# stm32f103cbt6.net
KiCad netlist of a schematic drawn in Altium Designer
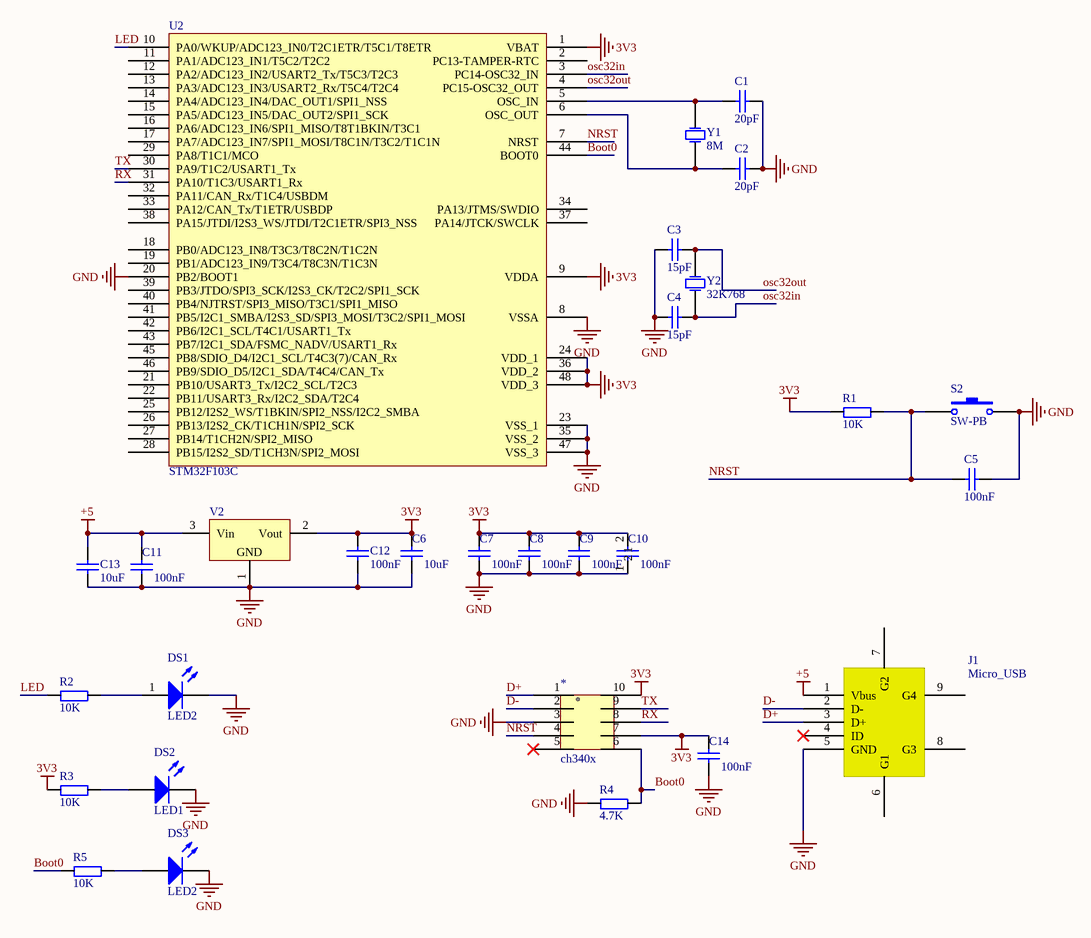
[diagram p0: stm32f103cbt6.SchDoc]

(export (version "E")
  (design (tool "Eeschema 10.0.6"))
  (components
    (comp (ref "*")
      (value "ch340x")
      (footprint "MSOP-10_L3.0-W3.0-P0.50-LS5.0-BL")
      (libsource (lib "常用元件库") (part "ch340x"))
    )
    (comp (ref "C1")
      (value "20pF")
      (footprint "C0603")
      (description "Capacitor")
      (fields (field (name "PUBLISHER") "Altium Limited"))
      (libsource (lib "Miscellaneous Devices") (part "Cap"))
    )
    (comp (ref "C2")
      (value "20pF")
      (footprint "C0603")
      (description "Capacitor")
      (fields (field (name "PUBLISHER") "Altium Limited"))
      (libsource (lib "Miscellaneous Devices") (part "Cap"))
    )
    (comp (ref "C3")
      (value "15pF")
      (footprint "C0603")
      (description "Capacitor")
      (fields (field (name "PUBLISHER") "Altium Limited"))
      (libsource (lib "Miscellaneous Devices") (part "Cap"))
    )
    (comp (ref "C4")
      (value "15pF")
      (footprint "C0603")
      (description "Capacitor")
      (fields (field (name "PUBLISHER") "Altium Limited"))
      (libsource (lib "Miscellaneous Devices") (part "Cap"))
    )
    (comp (ref "C5")
      (value "100nF")
      (footprint "C0603")
      (description "Capacitor")
      (fields (field (name "PUBLISHER") "Altium Limited"))
      (libsource (lib "Miscellaneous Devices") (part "Cap"))
    )
    (comp (ref "C6")
      (value "10uF")
      (footprint "C0603")
      (description "Capacitor")
      (fields (field (name "PUBLISHER") "Altium Limited"))
      (libsource (lib "Miscellaneous Devices") (part "Cap"))
    )
    (comp (ref "C7")
      (value "100nF")
      (footprint "C0603")
      (description "Capacitor")
      (fields (field (name "PUBLISHER") "Altium Limited"))
      (libsource (lib "Miscellaneous Devices") (part "Cap"))
    )
    (comp (ref "C8")
      (value "100nF")
      (footprint "C0603")
      (description "Capacitor")
      (fields (field (name "PUBLISHER") "Altium Limited"))
      (libsource (lib "Miscellaneous Devices") (part "Cap"))
    )
    (comp (ref "C9")
      (value "100nF")
      (footprint "C0603")
      (description "Capacitor")
      (fields (field (name "PUBLISHER") "Altium Limited"))
      (libsource (lib "Miscellaneous Devices") (part "Cap"))
    )
    (comp (ref "C10")
      (value "100nF")
      (footprint "C0603")
      (description "Capacitor")
      (fields (field (name "PUBLISHER") "Altium Limited"))
      (libsource (lib "") (part "Cap_1"))
    )
    (comp (ref "C11")
      (value "100nF")
      (footprint "C0603")
      (description "Capacitor")
      (fields (field (name "PUBLISHER") "Altium Limited"))
      (libsource (lib "Miscellaneous Devices") (part "Cap"))
    )
    (comp (ref "C12")
      (value "100nF")
      (footprint "C0603")
      (description "Capacitor")
      (fields (field (name "PUBLISHER") "Altium Limited"))
      (libsource (lib "Miscellaneous Devices") (part "Cap"))
    )
    (comp (ref "C13")
      (value "10uF")
      (footprint "C0603")
      (description "Capacitor")
      (fields (field (name "PUBLISHER") "Altium Limited"))
      (libsource (lib "Miscellaneous Devices") (part "Cap"))
    )
    (comp (ref "C14")
      (value "100nF")
      (footprint "C0603")
      (description "Capacitor")
      (fields (field (name "PUBLISHER") "Altium Limited"))
      (libsource (lib "Miscellaneous Devices") (part "Cap"))
    )
    (comp (ref "DS1")
      (value "LED2")
      (footprint "SMDLED")
      (description "Typical RED, GREEN, YELLOW, AMBER GaAs LED")
      (fields (field (name "PUBLISHER") "Altium Limited"))
      (libsource (lib "") (part "LED2_1"))
    )
    (comp (ref "DS2")
      (value "LED1")
      (footprint "SMDLED")
      (description "Typical RED, GREEN, YELLOW, AMBER GaAs LED")
      (fields (field (name "PUBLISHER") "Altium Limited"))
      (libsource (lib "朱雀F103开发板封装库") (part "LED2"))
    )
    (comp (ref "DS3")
      (value "LED2")
      (footprint "SMDLED")
      (description "Typical RED, GREEN, YELLOW, AMBER GaAs LED")
      (fields (field (name "PUBLISHER") "Altium Limited"))
      (libsource (lib "朱雀F103开发板封装库") (part "LED2"))
    )
    (comp (ref "J1")
      (value "Micro_USB")
      (footprint "MICRO-USB-SMD_MICROQTJ")
      (libsource (lib "Dr.Xiong_20160818") (part "Micro_USB"))
    )
    (comp (ref "R1") (value "10K") (footprint "0603P") (libsource (lib "朱雀F103开发板封装库") (part "R")))
    (comp (ref "R2") (value "10K") (footprint "0603P") (libsource (lib "朱雀F103开发板封装库") (part "R")))
    (comp (ref "R3") (value "10K") (footprint "0603P") (libsource (lib "朱雀F103开发板封装库") (part "R")))
    (comp (ref "R4") (value "4.7K") (footprint "0603P") (libsource (lib "朱雀F103开发板封装库") (part "R")))
    (comp (ref "R5") (value "10K") (footprint "0603P") (libsource (lib "朱雀F103开发板封装库") (part "R")))
    (comp (ref "S2")
      (value "SW-PB")
      (footprint "KEY-SMD_L3.9-W3.0-LS5.0")
      (description "Switch")
      (fields (field (name "PUBLISHER") "Altium Limited"))
      (libsource (lib "Miscellaneous Devices") (part "SW-PB"))
    )
    (comp (ref "U2")
      (value "STM32F103C")
      (footprint "LQFP-48_M")
      (description "STM32单片机48引脚")
      (libsource (lib "STM32芯片") (part "STM32F103C"))
    )
    (comp (ref "V2")
      (value "AMS1117-3V3")
      (footprint "SOT223_L")
      (description "三端稳压芯片")
      (fields (field (name "版权归属") "源创客"))
      (libsource (lib "1.3   - 电源类芯片") (part "AMS1117"))
    )
    (comp (ref "Y1")
      (value "8M")
      (footprint "XTAL(5032)")
      (description "Crystal Oscillator")
      (fields (field (name "PUBLISHER") "Altium Limited"))
      (libsource (lib "Miscellaneous Devices") (part "XTAL"))
    )
    (comp (ref "Y2")
      (value "32K768")
      (footprint "CRYSTAL-SMD_L3.2-W1.5-1")
      (description "Crystal Oscillator")
      (fields (field (name "PUBLISHER") "Altium Limited"))
      (libsource (lib "Miscellaneous Devices") (part "XTAL"))
    )
  )
  (nets
    (net (code "1") (name "+5") (class "Default")
      (node (ref "C11") (pin "2") (pinfunction "2_2") (pintype "passive"))
      (node (ref "C13") (pin "2") (pinfunction "2_2") (pintype "passive"))
      (node (ref "J1") (pin "1") (pinfunction "Vbus_1") (pintype "passive"))
      (node (ref "V2") (pin "3") (pinfunction "Vin_3") (pintype "passive"))
    )
    (net (code "2") (name "/Boot0") (class "Default")
      (node (ref "*") (pin "6") (pinfunction "DTR#_6") (pintype "passive"))
      (node (ref "R4") (pin "2") (pintype "passive"))
      (node (ref "R5") (pin "1") (pintype "passive"))
      (node (ref "U2") (pin "44") (pinfunction "BOOT0_44") (pintype "passive"))
    )
    (net (code "3") (name "/D+") (class "Default")
      (node (ref "*") (pin "1") (pinfunction "UD+_1") (pintype "passive"))
      (node (ref "J1") (pin "3") (pinfunction "D+_3") (pintype "passive"))
    )
    (net (code "4") (name "/D-") (class "Default")
      (node (ref "*") (pin "2") (pinfunction "UD-_2") (pintype "passive"))
      (node (ref "J1") (pin "2") (pinfunction "D-_2") (pintype "passive"))
    )
    (net (code "5") (name "/LED") (class "Default")
      (node (ref "R2") (pin "1") (pintype "passive"))
      (node (ref "U2") (pin "10") (pinfunction "PA0/WKUP/ADC123_IN0/T2C1ETR/T5C1/T8ETR_10") (pintype "passive"))
    )
    (net (code "6") (name "/NRST") (class "Default")
      (node (ref "*") (pin "4") (pinfunction "RTS#_4") (pintype "passive"))
      (node (ref "C5") (pin "1") (pinfunction "1_1") (pintype "passive"))
      (node (ref "R1") (pin "2") (pintype "passive"))
      (node (ref "S2") (pin "1") (pinfunction "1_1") (pintype "passive"))
      (node (ref "U2") (pin "7") (pinfunction "NRST_7") (pintype "passive"))
    )
    (net (code "7") (name "/RX") (class "Default")
      (node (ref "*") (pin "8") (pinfunction "TXD_8") (pintype "passive"))
      (node (ref "U2") (pin "31") (pinfunction "PA10/T1C3/USART1_Rx_31") (pintype "passive"))
    )
    (net (code "8") (name "/TX") (class "Default")
      (node (ref "*") (pin "9") (pinfunction "RXD_9") (pintype "passive"))
      (node (ref "U2") (pin "30") (pinfunction "PA9/T1C2/USART1_Tx_30") (pintype "passive"))
    )
    (net (code "9") (name "/osc32in") (class "Default")
      (node (ref "C4") (pin "2") (pinfunction "2_2") (pintype "passive"))
      (node (ref "U2") (pin "3") (pinfunction "PC14-OSC32_IN_3") (pintype "passive"))
      (node (ref "Y2") (pin "1") (pinfunction "OSC1_1") (pintype "passive"))
    )
    (net (code "10") (name "/osc32out") (class "Default")
      (node (ref "C3") (pin "2") (pinfunction "2_2") (pintype "passive"))
      (node (ref "U2") (pin "4") (pinfunction "PC15-OSC32_OUT_4") (pintype "passive"))
      (node (ref "Y2") (pin "2") (pinfunction "OSC2_2") (pintype "passive"))
    )
    (net (code "11") (name "3V3") (class "Default")
      (node (ref "*") (pin "10") (pinfunction "V3_10") (pintype "passive"))
      (node (ref "*") (pin "7") (pinfunction "VCC_7") (pintype "passive"))
      (node (ref "C10") (pin "2") (pinfunction "2_2") (pintype "passive"))
      (node (ref "C12") (pin "2") (pinfunction "2_2") (pintype "passive"))
      (node (ref "C14") (pin "2") (pinfunction "2_2") (pintype "passive"))
      (node (ref "C6") (pin "2") (pinfunction "2_2") (pintype "passive"))
      (node (ref "C7") (pin "2") (pinfunction "2_2") (pintype "passive"))
      (node (ref "C8") (pin "2") (pinfunction "2_2") (pintype "passive"))
      (node (ref "C9") (pin "2") (pinfunction "2_2") (pintype "passive"))
      (node (ref "R1") (pin "1") (pintype "passive"))
      (node (ref "R3") (pin "1") (pintype "passive"))
      (node (ref "U2") (pin "1") (pinfunction "VBAT_1") (pintype "passive"))
      (node (ref "U2") (pin "24") (pinfunction "VDD_1_24") (pintype "passive"))
      (node (ref "U2") (pin "36") (pinfunction "VDD_2_36") (pintype "passive"))
      (node (ref "U2") (pin "48") (pinfunction "VDD_3_48") (pintype "passive"))
      (node (ref "U2") (pin "9") (pinfunction "VDDA_9") (pintype "passive"))
      (node (ref "V2") (pin "2") (pinfunction "Vout_2") (pintype "passive"))
    )
    (net (code "12") (name "GND") (class "Default")
      (node (ref "*") (pin "3") (pinfunction "GND_3") (pintype "passive"))
      (node (ref "C1") (pin "2") (pinfunction "2_2") (pintype "passive"))
      (node (ref "C10") (pin "1") (pinfunction "1_1") (pintype "passive"))
      (node (ref "C11") (pin "1") (pinfunction "1_1") (pintype "passive"))
      (node (ref "C12") (pin "1") (pinfunction "1_1") (pintype "passive"))
      (node (ref "C13") (pin "1") (pinfunction "1_1") (pintype "passive"))
      (node (ref "C14") (pin "1") (pinfunction "1_1") (pintype "passive"))
      (node (ref "C2") (pin "2") (pinfunction "2_2") (pintype "passive"))
      (node (ref "C3") (pin "1") (pinfunction "1_1") (pintype "passive"))
      (node (ref "C4") (pin "1") (pinfunction "1_1") (pintype "passive"))
      (node (ref "C5") (pin "2") (pinfunction "2_2") (pintype "passive"))
      (node (ref "C6") (pin "1") (pinfunction "1_1") (pintype "passive"))
      (node (ref "C7") (pin "1") (pinfunction "1_1") (pintype "passive"))
      (node (ref "C8") (pin "1") (pinfunction "1_1") (pintype "passive"))
      (node (ref "C9") (pin "1") (pinfunction "1_1") (pintype "passive"))
      (node (ref "DS1") (pin "2") (pinfunction "K_2") (pintype "passive"))
      (node (ref "DS2") (pin "2") (pinfunction "K_2") (pintype "passive"))
      (node (ref "DS3") (pin "2") (pinfunction "K_2") (pintype "passive"))
      (node (ref "J1") (pin "5") (pinfunction "GND_5") (pintype "passive"))
      (node (ref "R4") (pin "1") (pintype "passive"))
      (node (ref "S2") (pin "2") (pinfunction "2_2") (pintype "passive"))
      (node (ref "U2") (pin "20") (pinfunction "PB2/BOOT1_20") (pintype "passive"))
      (node (ref "U2") (pin "23") (pinfunction "VSS_1_23") (pintype "passive"))
      (node (ref "U2") (pin "35") (pinfunction "VSS_2_35") (pintype "passive"))
      (node (ref "U2") (pin "47") (pinfunction "VSS_3_47") (pintype "passive"))
      (node (ref "U2") (pin "8") (pinfunction "VSSA_8") (pintype "passive"))
      (node (ref "V2") (pin "1") (pinfunction "GND_1") (pintype "passive"))
    )
    (net (code "13") (name "Net-(DS1-A)") (class "Default")
      (node (ref "DS1") (pin "1") (pinfunction "A_1") (pintype "passive"))
      (node (ref "R2") (pin "2") (pintype "passive"))
    )
    (net (code "14") (name "Net-(DS2-A)") (class "Default")
      (node (ref "DS2") (pin "1") (pinfunction "A_1") (pintype "passive"))
      (node (ref "R3") (pin "2") (pintype "passive"))
    )
    (net (code "15") (name "Net-(DS3-A)") (class "Default")
      (node (ref "DS3") (pin "1") (pinfunction "A_1") (pintype "passive"))
      (node (ref "R5") (pin "2") (pintype "passive"))
    )
    (net (code "16") (name "Net-(U2-OSC_IN)") (class "Default")
      (node (ref "C1") (pin "1") (pinfunction "1_1") (pintype "passive"))
      (node (ref "U2") (pin "5") (pinfunction "OSC_IN_5") (pintype "passive"))
      (node (ref "Y1") (pin "2") (pinfunction "OSC2_2") (pintype "passive"))
    )
    (net (code "17") (name "Net-(U2-OSC_OUT)") (class "Default")
      (node (ref "C2") (pin "1") (pinfunction "1_1") (pintype "passive"))
      (node (ref "U2") (pin "6") (pinfunction "OSC_OUT_6") (pintype "passive"))
      (node (ref "Y1") (pin "1") (pinfunction "OSC1_1") (pintype "passive"))
    )
    (net (code "18") (name "unconnected-(*-CTS#-Pad5)") (class "Default")
      (node (ref "*") (pin "5") (pinfunction "CTS#_5") (pintype "passive+no_connect"))
    )
    (net (code "19") (name "unconnected-(J1-G1-Pad6)") (class "Default")
      (node (ref "J1") (pin "6") (pinfunction "G1_6") (pintype "passive"))
    )
    (net (code "20") (name "unconnected-(J1-G2-Pad7)") (class "Default")
      (node (ref "J1") (pin "7") (pinfunction "G2_7") (pintype "passive"))
    )
    (net (code "21") (name "unconnected-(J1-G3-Pad8)") (class "Default")
      (node (ref "J1") (pin "8") (pinfunction "G3_8") (pintype "passive"))
    )
    (net (code "22") (name "unconnected-(J1-G4-Pad9)") (class "Default")
      (node (ref "J1") (pin "9") (pinfunction "G4_9") (pintype "passive"))
    )
    (net (code "23") (name "unconnected-(J1-ID-Pad4)") (class "Default")
      (node (ref "J1") (pin "4") (pinfunction "ID_4") (pintype "passive+no_connect"))
    )
    (net (code "24") (name "unconnected-(U2-PA1{slash}ADC123_IN1{slash}T5C2{slash}T2C2-Pad11)") (class "Default")
      (node (ref "U2") (pin "11") (pinfunction "PA1/ADC123_IN1/T5C2/T2C2_11") (pintype "passive"))
    )
    (net (code "25") (name "unconnected-(U2-PA2{slash}ADC123_IN2{slash}USART2_Tx{slash}T5C3{slash}T2C3-Pad12)") (class "Default")
      (node (ref "U2") (pin "12") (pinfunction "PA2/ADC123_IN2/USART2_Tx/T5C3/T2C3_12") (pintype "passive"))
    )
    (net (code "26") (name "unconnected-(U2-PA3{slash}ADC123_IN3{slash}USART2_Rx{slash}T5C4{slash}T2C4-Pad13)") (class "Default")
      (node (ref "U2") (pin "13") (pinfunction "PA3/ADC123_IN3/USART2_Rx/T5C4/T2C4_13") (pintype "passive"))
    )
    (net (code "27") (name "unconnected-(U2-PA4{slash}ADC123_IN4{slash}DAC_OUT1{slash}SPI1_NSS-Pad14)") (class "Default")
      (node (ref "U2") (pin "14") (pinfunction "PA4/ADC123_IN4/DAC_OUT1/SPI1_NSS_14") (pintype "passive"))
    )
    (net (code "28") (name "unconnected-(U2-PA5{slash}ADC123_IN5{slash}DAC_OUT2{slash}SPI1_SCK-Pad15)") (class "Default")
      (node (ref "U2") (pin "15") (pinfunction "PA5/ADC123_IN5/DAC_OUT2/SPI1_SCK_15") (pintype "passive"))
    )
    (net (code "29") (name "unconnected-(U2-PA6{slash}ADC123_IN6{slash}SPI1_MISO{slash}T8T1BKIN{slash}T3C1-Pad16)") (class "Default")
      (node (ref "U2") (pin "16") (pinfunction "PA6/ADC123_IN6/SPI1_MISO/T8T1BKIN/T3C1_16") (pintype "passive"))
    )
    (net (code "30") (name "unconnected-(U2-PA7{slash}ADC123_IN7{slash}SPI1_MOSI{slash}T8C1N{slash}T3C2{slash}T1C1N-Pad17)") (class "Default")
      (node (ref "U2") (pin "17") (pinfunction "PA7/ADC123_IN7/SPI1_MOSI/T8C1N/T3C2/T1C1N_17") (pintype "passive"))
    )
    (net (code "31") (name "unconnected-(U2-PA8{slash}T1C1{slash}MCO-Pad29)") (class "Default")
      (node (ref "U2") (pin "29") (pinfunction "PA8/T1C1/MCO_29") (pintype "passive"))
    )
    (net (code "32") (name "unconnected-(U2-PA11{slash}CAN_Rx{slash}T1C4{slash}USBDM-Pad32)") (class "Default")
      (node (ref "U2") (pin "32") (pinfunction "PA11/CAN_Rx/T1C4/USBDM_32") (pintype "passive"))
    )
    (net (code "33") (name "unconnected-(U2-PA12{slash}CAN_Tx{slash}T1ETR{slash}USBDP-Pad33)") (class "Default")
      (node (ref "U2") (pin "33") (pinfunction "PA12/CAN_Tx/T1ETR/USBDP_33") (pintype "passive"))
    )
    (net (code "34") (name "unconnected-(U2-PA13{slash}JTMS{slash}SWDIO-Pad34)") (class "Default")
      (node (ref "U2") (pin "34") (pinfunction "PA13/JTMS/SWDIO_34") (pintype "passive"))
    )
    (net (code "35") (name "unconnected-(U2-PA14{slash}JTCK{slash}SWCLK-Pad37)") (class "Default")
      (node (ref "U2") (pin "37") (pinfunction "PA14/JTCK/SWCLK_37") (pintype "passive"))
    )
    (net (code "36") (name "unconnected-(U2-PA15{slash}JTDI{slash}I2S3_WS{slash}JTDI{slash}T2C1ETR{slash}SPI3_NSS-Pad38)") (class "Default")
      (node (ref "U2") (pin "38") (pinfunction "PA15/JTDI/I2S3_WS/JTDI/T2C1ETR/SPI3_NSS_38") (pintype "passive"))
    )
    (net (code "37") (name "unconnected-(U2-PB0{slash}ADC123_IN8{slash}T3C3{slash}T8C2N{slash}T1C2N-Pad18)") (class "Default")
      (node (ref "U2") (pin "18") (pinfunction "PB0/ADC123_IN8/T3C3/T8C2N/T1C2N_18") (pintype "passive"))
    )
    (net (code "38") (name "unconnected-(U2-PB1{slash}ADC123_IN9{slash}T3C4{slash}T8C3N{slash}T1C3N-Pad19)") (class "Default")
      (node (ref "U2") (pin "19") (pinfunction "PB1/ADC123_IN9/T3C4/T8C3N/T1C3N_19") (pintype "passive"))
    )
    (net (code "39") (name "unconnected-(U2-PB3{slash}JTDO{slash}SPI3_SCK{slash}I2S3_CK{slash}T2C2{slash}SPI1_SCK-Pad39)") (class "Default")
      (node (ref "U2") (pin "39") (pinfunction "PB3/JTDO/SPI3_SCK/I2S3_CK/T2C2/SPI1_SCK_39") (pintype "passive"))
    )
    (net (code "40") (name "unconnected-(U2-PB4{slash}NJTRST{slash}SPI3_MISO{slash}T3C1{slash}SPI1_MISO-Pad40)") (class "Default")
      (node (ref "U2") (pin "40") (pinfunction "PB4/NJTRST/SPI3_MISO/T3C1/SPI1_MISO_40") (pintype "passive"))
    )
    (net (code "41") (name "unconnected-(U2-PB5{slash}I2C1_SMBA{slash}I2S3_SD{slash}SPI3_MOSI{slash}T3C2{slash}SPI1_MOSI-Pad41)") (class "Default")
      (node (ref "U2") (pin "41") (pinfunction "PB5/I2C1_SMBA/I2S3_SD/SPI3_MOSI/T3C2/SPI1_MOSI_41") (pintype "passive"))
    )
    (net (code "42") (name "unconnected-(U2-PB6{slash}I2C1_SCL{slash}T4C1{slash}USART1_Tx-Pad42)") (class "Default")
      (node (ref "U2") (pin "42") (pinfunction "PB6/I2C1_SCL/T4C1/USART1_Tx_42") (pintype "passive"))
    )
    (net (code "43") (name "unconnected-(U2-PB7{slash}I2C1_SDA{slash}FSMC_NADV{slash}USART1_Rx-Pad43)") (class "Default")
      (node (ref "U2") (pin "43") (pinfunction "PB7/I2C1_SDA/FSMC_NADV/USART1_Rx_43") (pintype "passive"))
    )
    (net (code "44") (name "unconnected-(U2-PB8{slash}SDIO_D4{slash}I2C1_SCL{slash}T4C3(7){slash}CAN_Rx-Pad45)") (class "Default")
      (node (ref "U2") (pin "45") (pinfunction "PB8/SDIO_D4/I2C1_SCL/T4C3(7)/CAN_Rx_45") (pintype "passive"))
    )
    (net (code "45") (name "unconnected-(U2-PB9{slash}SDIO_D5{slash}I2C1_SDA{slash}T4C4{slash}CAN_Tx-Pad46)") (class "Default")
      (node (ref "U2") (pin "46") (pinfunction "PB9/SDIO_D5/I2C1_SDA/T4C4/CAN_Tx_46") (pintype "passive"))
    )
    (net (code "46") (name "unconnected-(U2-PB10{slash}USART3_Tx{slash}I2C2_SCL{slash}T2C3-Pad21)") (class "Default")
      (node (ref "U2") (pin "21") (pinfunction "PB10/USART3_Tx/I2C2_SCL/T2C3_21") (pintype "passive"))
    )
    (net (code "47") (name "unconnected-(U2-PB11{slash}USART3_Rx{slash}I2C2_SDA{slash}T2C4-Pad22)") (class "Default")
      (node (ref "U2") (pin "22") (pinfunction "PB11/USART3_Rx/I2C2_SDA/T2C4_22") (pintype "passive"))
    )
    (net (code "48") (name "unconnected-(U2-PB12{slash}I2S2_WS{slash}T1BKIN{slash}SPI2_NSS{slash}I2C2_SMBA-Pad25)") (class "Default")
      (node (ref "U2") (pin "25") (pinfunction "PB12/I2S2_WS/T1BKIN/SPI2_NSS/I2C2_SMBA_25") (pintype "passive"))
    )
    (net (code "49") (name "unconnected-(U2-PB13{slash}I2S2_CK{slash}T1CH1N{slash}SPI2_SCK-Pad26)") (class "Default")
      (node (ref "U2") (pin "26") (pinfunction "PB13/I2S2_CK/T1CH1N/SPI2_SCK_26") (pintype "passive"))
    )
    (net (code "50") (name "unconnected-(U2-PB14{slash}T1CH2N{slash}SPI2_MISO-Pad27)") (class "Default")
      (node (ref "U2") (pin "27") (pinfunction "PB14/T1CH2N/SPI2_MISO_27") (pintype "passive"))
    )
    (net (code "51") (name "unconnected-(U2-PB15{slash}I2S2_SD{slash}T1CH3N{slash}SPI2_MOSI-Pad28)") (class "Default")
      (node (ref "U2") (pin "28") (pinfunction "PB15/I2S2_SD/T1CH3N/SPI2_MOSI_28") (pintype "passive"))
    )
    (net (code "52") (name "unconnected-(U2-PC13-TAMPER-RTC-Pad2)") (class "Default")
      (node (ref "U2") (pin "2") (pinfunction "PC13-TAMPER-RTC_2") (pintype "passive"))
    )
  )
)
